# geiger_PSU.net
KiCad netlist of a schematic drawn in EAGLE
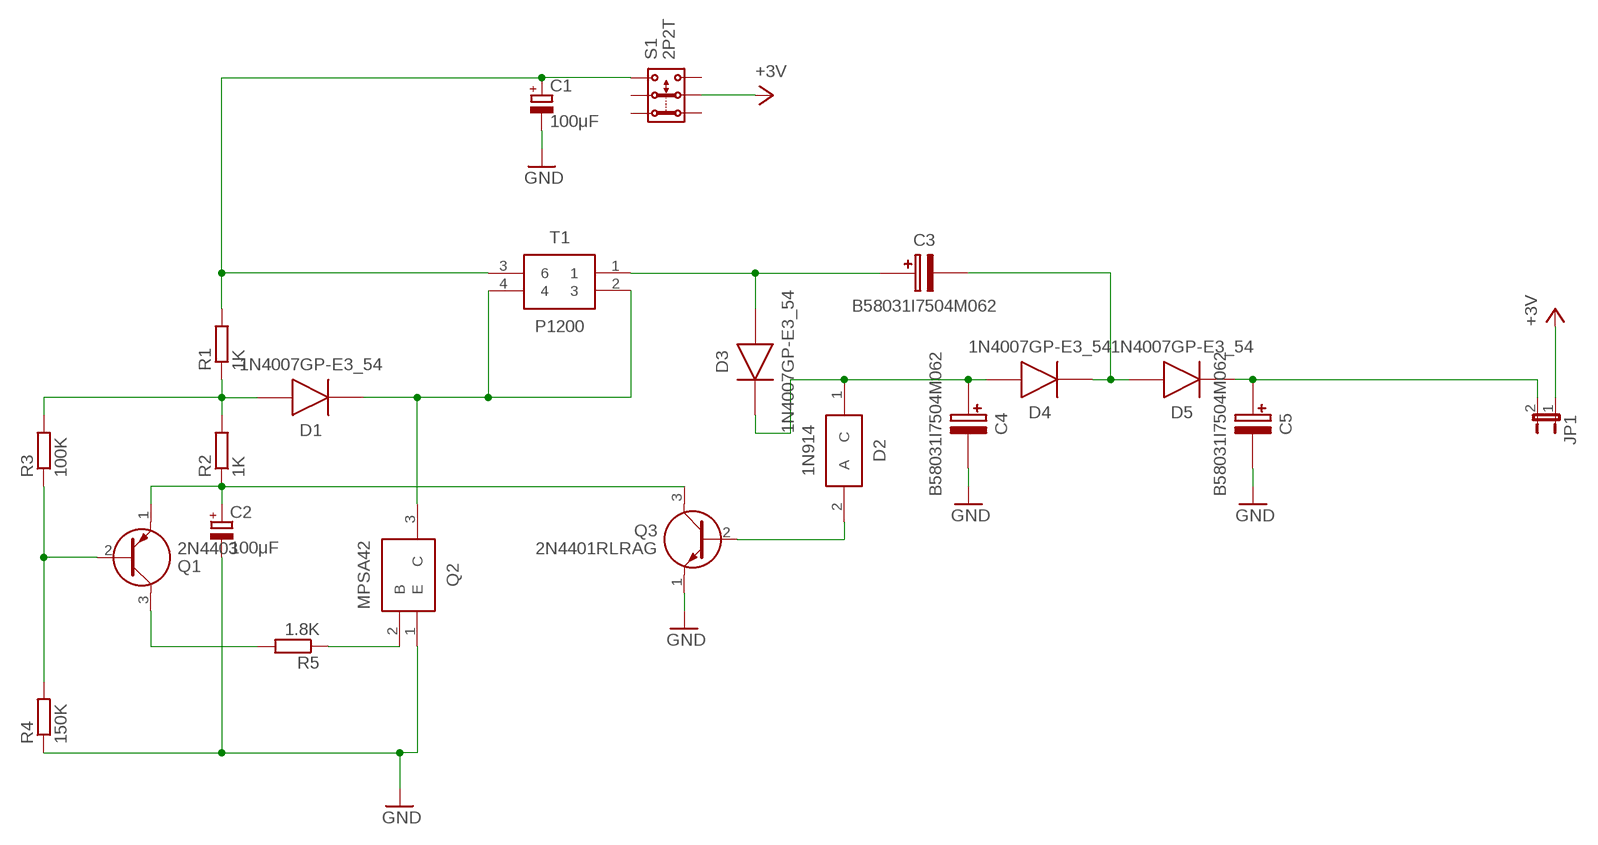
[diagram p0: schematic, sheet 1]

(export (version "E")
  (design (tool "Eeschema 10.0.6"))
  (components
    (comp (ref "C1")
      (value "100μF")
      (footprint "eagle-import:085CS_1AR")
      (libsource (lib "eagle-import") (part "CPOL-EU085CS-1AR"))
    )
    (comp (ref "C2")
      (value "100μF")
      (footprint "eagle-import:085CS_1AR")
      (libsource (lib "eagle-import") (part "CPOL-EU085CS-1AR"))
    )
    (comp (ref "C3")
      (value "B58031I7504M062")
      (footprint "eagle-import:CAPPC10878X450N")
      (libsource (lib "eagle-import") (part "B58031I7504M062"))
    )
    (comp (ref "C4")
      (value "B58031I7504M062")
      (footprint "eagle-import:CAPPC10878X450N")
      (libsource (lib "eagle-import") (part "B58031I7504M062"))
    )
    (comp (ref "C5")
      (value "B58031I7504M062")
      (footprint "eagle-import:CAPPC10878X450N")
      (libsource (lib "eagle-import") (part "B58031I7504M062"))
    )
    (comp (ref "D1")
      (value "1N4007GP-E3_54")
      (footprint "eagle-import:DIOAD1405W86L465D235")
      (fields
        (field (name "MANUFACTURER_PART_NUMBER") "1N4007GP-E3/54")
        (field (name "RS_PART_NUMBER") "7087984P")
      )
      (libsource (lib "eagle-import") (part "1N4007GP-E3_54"))
    )
    (comp (ref "D2")
      (value "1N914")
      (footprint "eagle-import:DIO_1N914")
      (libsource (lib "eagle-import") (part "1N914"))
    )
    (comp (ref "D3")
      (value "1N4007GP-E3_54")
      (footprint "eagle-import:DIOAD1405W86L465D235")
      (fields
        (field (name "MANUFACTURER_PART_NUMBER") "1N4007GP-E3/54")
        (field (name "RS_PART_NUMBER") "7087984P")
      )
      (libsource (lib "eagle-import") (part "1N4007GP-E3_54"))
    )
    (comp (ref "D4")
      (value "1N4007GP-E3_54")
      (footprint "eagle-import:DIOAD1405W86L465D235")
      (fields
        (field (name "MANUFACTURER_PART_NUMBER") "1N4007GP-E3/54")
        (field (name "RS_PART_NUMBER") "7087984P")
      )
      (libsource (lib "eagle-import") (part "1N4007GP-E3_54"))
    )
    (comp (ref "D5")
      (value "1N4007GP-E3_54")
      (footprint "eagle-import:DIOAD1405W86L465D235")
      (fields
        (field (name "MANUFACTURER_PART_NUMBER") "1N4007GP-E3/54")
        (field (name "RS_PART_NUMBER") "7087984P")
      )
      (libsource (lib "eagle-import") (part "1N4007GP-E3_54"))
    )
    (comp (ref "JP1")
      (value "JP1E")
      (footprint "eagle-import:JP1")
      (libsource (lib "eagle-import") (part "JP1E"))
    )
    (comp (ref "Q1")
      (value "2N4403")
      (footprint "eagle-import:TO160P419X482X533-3P")
      (libsource (lib "eagle-import") (part "2N4403"))
    )
    (comp (ref "Q2")
      (value "MPSA42")
      (footprint "eagle-import:TO127P254X635-3")
      (fields (field (name "RS_PART_NUMBER") "1241357"))
      (libsource (lib "eagle-import") (part "MPSA42"))
    )
    (comp (ref "Q3")
      (value "2N4401RLRAG")
      (footprint "eagle-import:TO-92")
      (fields (field (name "RS_PART_NUMBER") "7925476"))
      (libsource (lib "eagle-import") (part "2N4401RLRAG"))
    )
    (comp (ref "R1")
      (value "1K")
      (footprint "eagle-import:0204V")
      (libsource (lib "eagle-import") (part "R-EU_0204/2V"))
    )
    (comp (ref "R2")
      (value "1K")
      (footprint "eagle-import:0204V")
      (libsource (lib "eagle-import") (part "R-EU_0204/2V"))
    )
    (comp (ref "R3")
      (value "100K")
      (footprint "eagle-import:0204V")
      (libsource (lib "eagle-import") (part "R-EU_0204/2V"))
    )
    (comp (ref "R4")
      (value "150K")
      (footprint "eagle-import:0204V")
      (libsource (lib "eagle-import") (part "R-EU_0204/2V"))
    )
    (comp (ref "R5")
      (value "1.8K")
      (footprint "eagle-import:0204V")
      (libsource (lib "eagle-import") (part "R-EU_0204/2V"))
    )
    (comp (ref "S1")
      (value "2P2T")
      (footprint "eagle-import:2P2T")
      (libsource (lib "eagle-import") (part "2P2T"))
    )
    (comp (ref "T1")
      (value "P1200")
      (footprint "eagle-import:HDRV4W100P762X1270_2X2_1800X18")
      (libsource (lib "eagle-import") (part "P1200"))
    )
  )
  (nets
    (net (code "1") (name "+3V") (class "Default")
      (node (ref "JP1") (pin "1") (pinfunction "1_1") (pintype "passive"))
      (node (ref "S1") (pin "2.2") (pinfunction "2.2_2.2") (pintype "passive"))
    )
    (net (code "2") (name "GND") (class "Default")
      (node (ref "C1") (pin "-") (pinfunction "-_-") (pintype "passive"))
      (node (ref "C2") (pin "-") (pinfunction "-_-") (pintype "passive"))
      (node (ref "C4") (pin "2") (pinfunction "-_2") (pintype "bidirectional"))
      (node (ref "C5") (pin "2") (pinfunction "-_2") (pintype "bidirectional"))
      (node (ref "Q2") (pin "1") (pinfunction "E_1") (pintype "passive"))
      (node (ref "Q3") (pin "1") (pinfunction "E_1") (pintype "input"))
      (node (ref "R4") (pin "1") (pinfunction "1_1") (pintype "passive"))
    )
    (net (code "3") (name "Net-(C3-+)") (class "Default")
      (node (ref "C3") (pin "1") (pinfunction "+_1") (pintype "bidirectional"))
      (node (ref "D3") (pin "2") (pinfunction "A_2") (pintype "bidirectional"))
      (node (ref "T1") (pin "1") (pinfunction "1_1") (pintype "passive"))
    )
    (net (code "4") (name "Net-(C3--)") (class "Default")
      (node (ref "C3") (pin "2") (pinfunction "-_2") (pintype "bidirectional"))
      (node (ref "D4") (pin "1") (pinfunction "K_1") (pintype "bidirectional"))
      (node (ref "D5") (pin "2") (pinfunction "A_2") (pintype "bidirectional"))
    )
    (net (code "5") (name "Net-(C4-+)") (class "Default")
      (node (ref "C4") (pin "1") (pinfunction "+_1") (pintype "bidirectional"))
      (node (ref "D2") (pin "1") (pinfunction "C_1") (pintype "passive"))
      (node (ref "D3") (pin "1") (pinfunction "K_1") (pintype "bidirectional"))
      (node (ref "D4") (pin "2") (pinfunction "A_2") (pintype "bidirectional"))
    )
    (net (code "6") (name "Net-(C5-+)") (class "Default")
      (node (ref "C5") (pin "1") (pinfunction "+_1") (pintype "bidirectional"))
      (node (ref "D5") (pin "1") (pinfunction "K_1") (pintype "bidirectional"))
      (node (ref "JP1") (pin "2") (pinfunction "2_2") (pintype "passive"))
    )
    (net (code "7") (name "Net-(D1-A)") (class "Default")
      (node (ref "D1") (pin "2") (pinfunction "A_2") (pintype "bidirectional"))
      (node (ref "R1") (pin "1") (pinfunction "1_1") (pintype "passive"))
      (node (ref "R2") (pin "2") (pinfunction "2_2") (pintype "passive"))
      (node (ref "R3") (pin "2") (pinfunction "2_2") (pintype "passive"))
    )
    (net (code "8") (name "Net-(D1-K)") (class "Default")
      (node (ref "D1") (pin "1") (pinfunction "K_1") (pintype "bidirectional"))
      (node (ref "Q2") (pin "3") (pinfunction "C_3") (pintype "passive"))
      (node (ref "T1") (pin "2") (pinfunction "3_2") (pintype "passive"))
      (node (ref "T1") (pin "4") (pinfunction "4_4") (pintype "passive"))
    )
    (net (code "9") (name "Net-(D2-A)") (class "Default")
      (node (ref "D2") (pin "2") (pinfunction "A_2") (pintype "passive"))
      (node (ref "Q3") (pin "2") (pinfunction "B_2") (pintype "input"))
    )
    (net (code "10") (name "Net-(Q1-B)") (class "Default")
      (node (ref "Q1") (pin "2") (pinfunction "B_2") (pintype "input"))
      (node (ref "R3") (pin "1") (pinfunction "1_1") (pintype "passive"))
      (node (ref "R4") (pin "2") (pinfunction "2_2") (pintype "passive"))
    )
    (net (code "11") (name "Net-(Q1-C)") (class "Default")
      (node (ref "Q1") (pin "3") (pinfunction "C_3") (pintype "input"))
      (node (ref "R5") (pin "2") (pinfunction "2_2") (pintype "passive"))
    )
    (net (code "12") (name "Net-(Q1-E)") (class "Default")
      (node (ref "C2") (pin "+") (pinfunction "+_+") (pintype "passive"))
      (node (ref "Q1") (pin "1") (pinfunction "E_1") (pintype "input"))
      (node (ref "Q3") (pin "3") (pinfunction "C_3") (pintype "input"))
      (node (ref "R2") (pin "1") (pinfunction "1_1") (pintype "passive"))
    )
    (net (code "13") (name "Net-(Q2-B)") (class "Default")
      (node (ref "Q2") (pin "2") (pinfunction "B_2") (pintype "passive"))
      (node (ref "R5") (pin "1") (pinfunction "1_1") (pintype "passive"))
    )
    (net (code "14") (name "Net-(T1-6)") (class "Default")
      (node (ref "C1") (pin "+") (pinfunction "+_+") (pintype "passive"))
      (node (ref "R1") (pin "2") (pinfunction "2_2") (pintype "passive"))
      (node (ref "S1") (pin "3.1") (pinfunction "3.1_3.1") (pintype "passive"))
      (node (ref "T1") (pin "3") (pinfunction "6_3") (pintype "passive"))
    )
    (net (code "15") (name "unconnected-(S1-Pad1.1)") (class "Default")
      (node (ref "S1") (pin "1.1") (pinfunction "1.1_1.1") (pintype "passive"))
    )
    (net (code "16") (name "unconnected-(S1-Pad1.2)") (class "Default")
      (node (ref "S1") (pin "1.2") (pinfunction "1.2_1.2") (pintype "passive"))
    )
    (net (code "17") (name "unconnected-(S1-Pad2.1)") (class "Default")
      (node (ref "S1") (pin "2.1") (pinfunction "2.1_2.1") (pintype "passive"))
    )
    (net (code "18") (name "unconnected-(S1-Pad3.2)") (class "Default")
      (node (ref "S1") (pin "3.2") (pinfunction "3.2_3.2") (pintype "passive"))
    )
  )
)
